# DM1098FFC_USB.net
KiCad netlist of a schematic drawn in Altium Designer
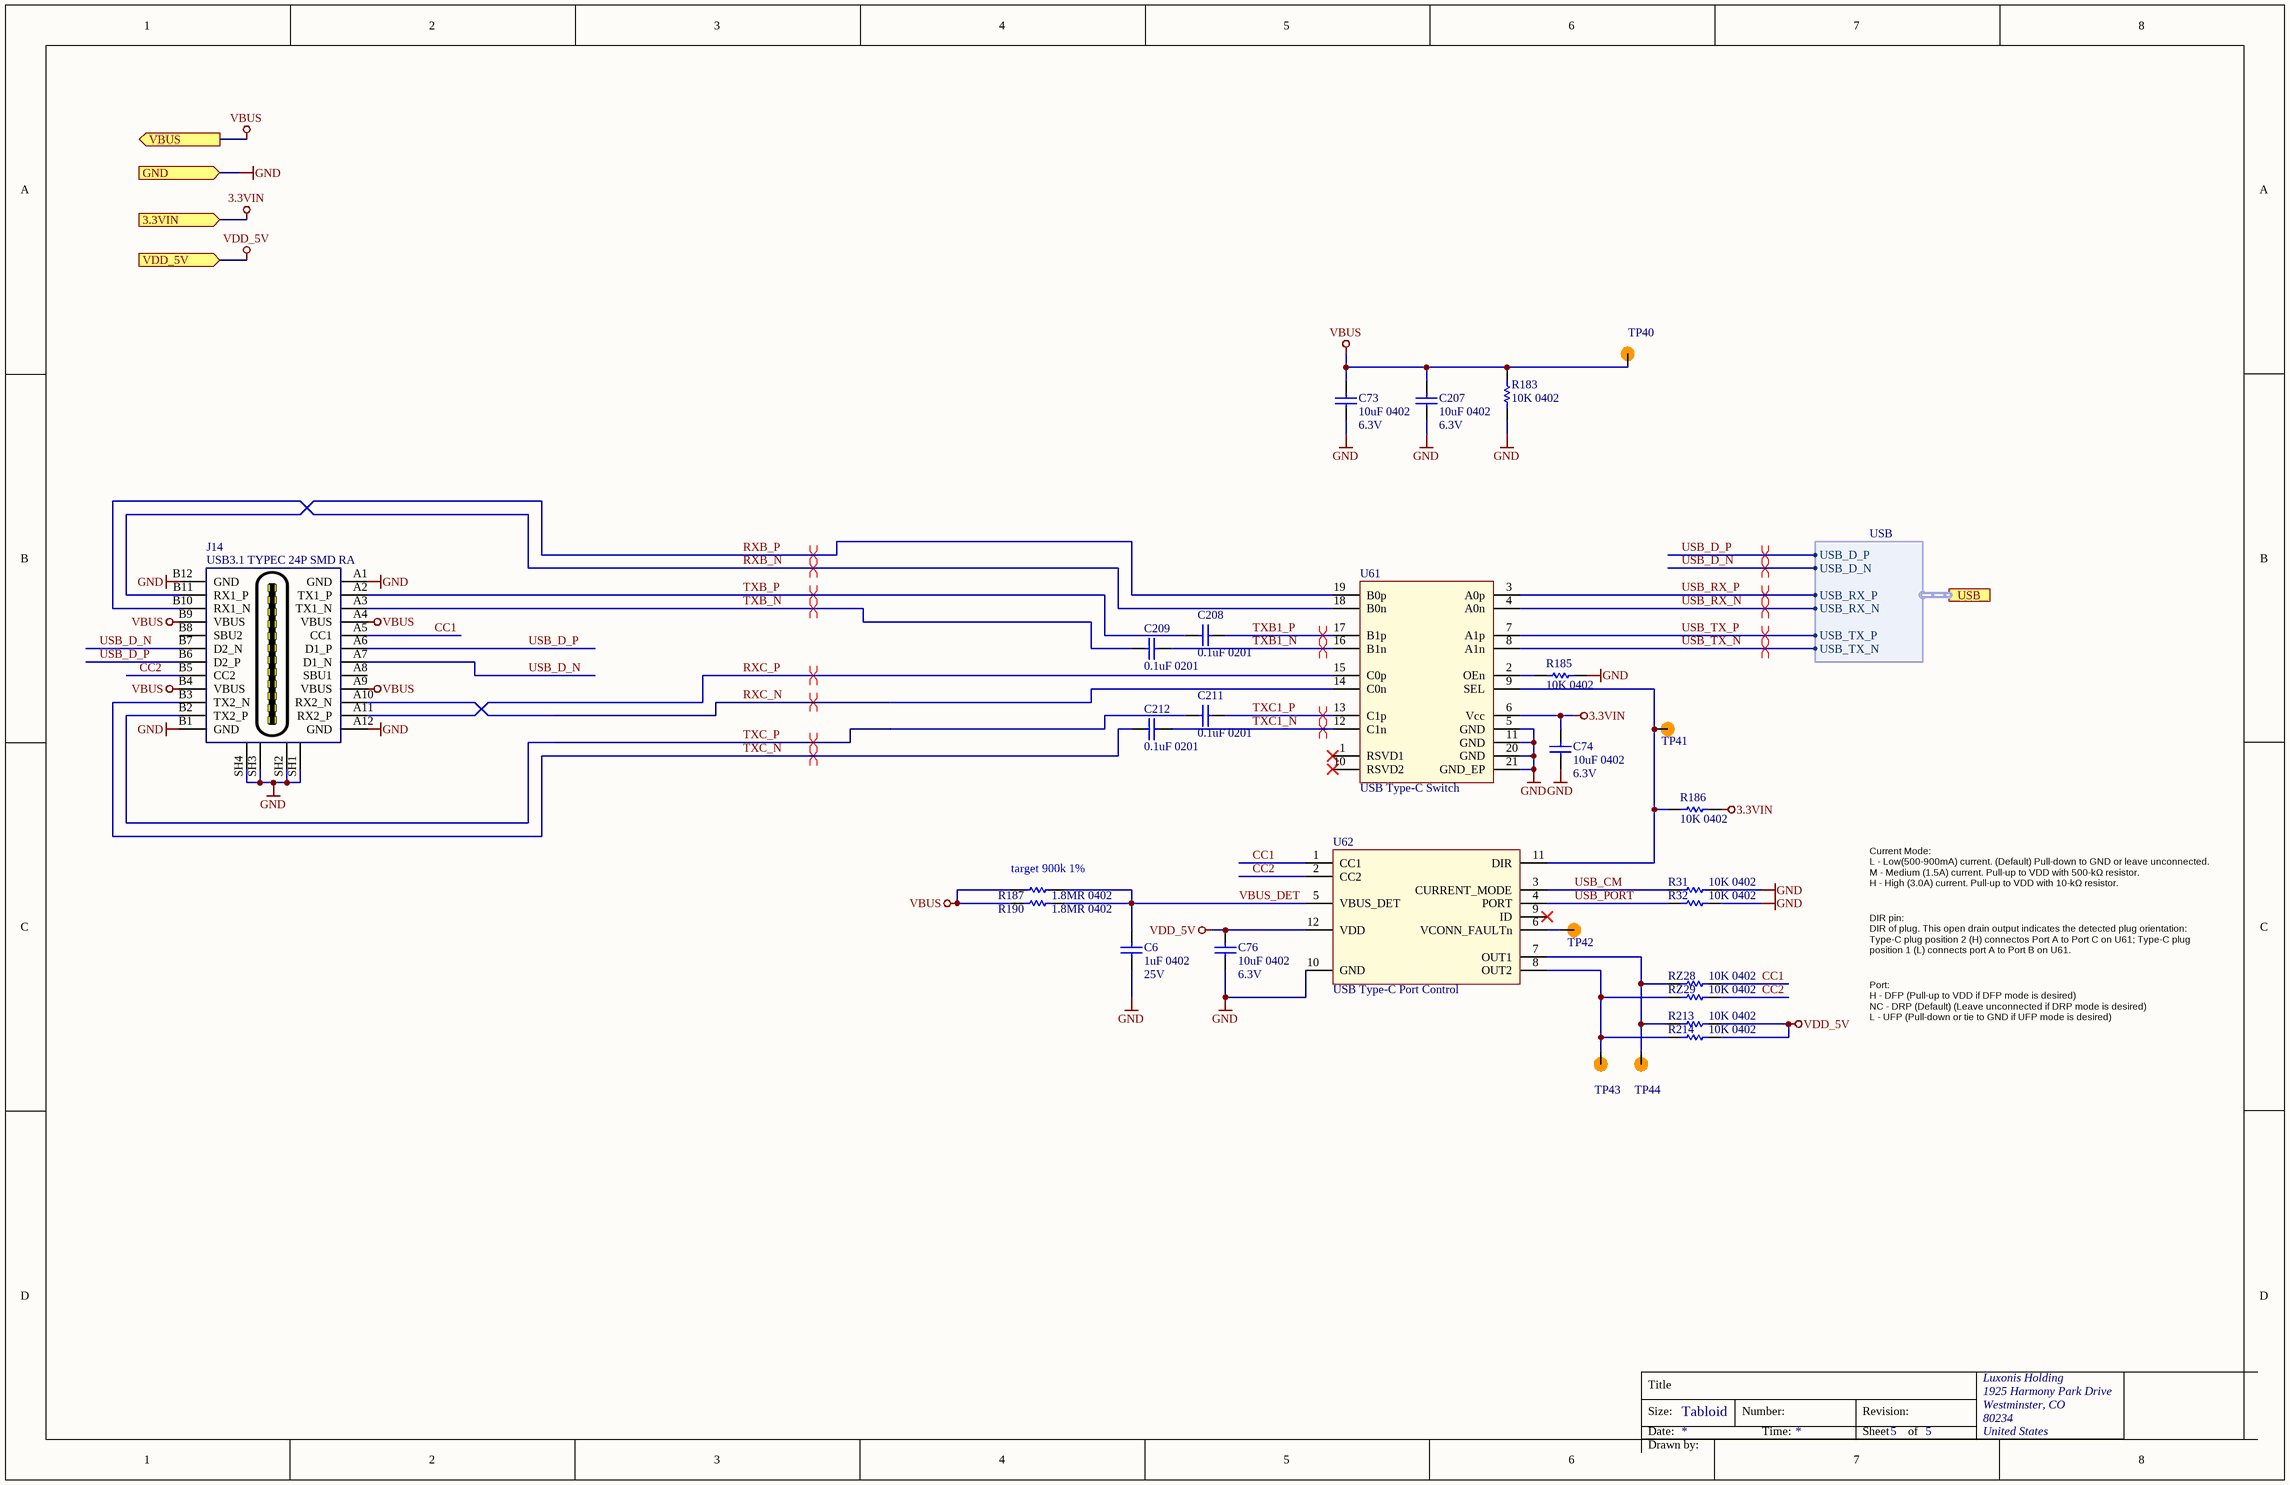
[diagram p0: DM1098FFC_USB.SchDoc]

(export (version "E")
  (design (tool "Eeschema 10.0.6"))
  (components
    (comp (ref "C6")
      (value "1uF 0402")
      (footprint "CAP_Altium_Vault_Generic:CAPC0402(1005)70_N")
      (description "CAP CER 1UF 25V X5R 0402 10%")
      (fields
        (field (name "TOLERANCE") "10%")
        (field (name "VOLTAGE") "25V")
        (field (name "VOLTAGE RATING") "25V")
      )
      (libsource (lib "LuxonisMaster") (part "GRM155R61E105KA12D"))
    )
    (comp (ref "C73")
      (value "10uF 0402")
      (footprint "CAP_Altium_Vault_Generic:CAPC0402(1005)70_N")
      (description "CAP CER 10UF 6.3V X5R 0402 20%")
      (fields (field (name "TOLERANCE") "20%") (field (name "VOLTAGE RATING") "6.3V"))
      (libsource (lib "LuxonisMaster") (part "GRM155R60J106ME15D"))
    )
    (comp (ref "C74")
      (value "10uF 0402")
      (footprint "CAP_Altium_Vault_Generic:CAPC0402(1005)70_N")
      (description "CAP CER 10UF 6.3V X5R 0402 20%")
      (fields (field (name "TOLERANCE") "20%") (field (name "VOLTAGE RATING") "6.3V"))
      (libsource (lib "LuxonisMaster") (part "GRM155R60J106ME15D"))
    )
    (comp (ref "C76")
      (value "10uF 0402")
      (footprint "CAP_Altium_Vault_Generic:CAPC0402(1005)70_N")
      (description "CAP CER 10UF 6.3V X5R 0402 20%")
      (fields (field (name "TOLERANCE") "20%") (field (name "VOLTAGE RATING") "6.3V"))
      (libsource (lib "LuxonisMaster") (part "GRM155R60J106ME15D"))
    )
    (comp (ref "C207")
      (value "10uF 0402")
      (footprint "CAP_Altium_Vault_Generic:CAPC0402(1005)70_N")
      (description "CAP CER 10UF 6.3V X5R 0402 20%")
      (fields (field (name "TOLERANCE") "20%") (field (name "VOLTAGE RATING") "6.3V"))
      (libsource (lib "LuxonisMaster") (part "GRM155R60J106ME15D"))
    )
    (comp (ref "C208")
      (value "0.1uF 0201")
      (footprint "CAP_Altium_Vault_Generic:CAPC0201(0603)33_L")
      (description "CAP CER 0.1UF 10V X5R 0201")
      (fields (field (name "TOLERANCE") "10%") (field (name "VOLTAGE") "10V"))
      (libsource (lib "LuxonisMaster") (part "GRM033R61A104KE15D"))
    )
    (comp (ref "C209")
      (value "0.1uF 0201")
      (footprint "CAP_Altium_Vault_Generic:CAPC0201(0603)33_L")
      (description "CAP CER 0.1UF 10V X5R 0201")
      (fields (field (name "TOLERANCE") "10%") (field (name "VOLTAGE") "10V"))
      (libsource (lib "LuxonisMaster") (part "GRM033R61A104KE15D"))
    )
    (comp (ref "C211")
      (value "0.1uF 0201")
      (footprint "CAP_Altium_Vault_Generic:CAPC0201(0603)33_L")
      (description "CAP CER 0.1UF 10V X5R 0201")
      (fields (field (name "TOLERANCE") "10%") (field (name "VOLTAGE") "10V"))
      (libsource (lib "LuxonisMaster") (part "GRM033R61A104KE15D"))
    )
    (comp (ref "C212")
      (value "0.1uF 0201")
      (footprint "CAP_Altium_Vault_Generic:CAPC0201(0603)33_L")
      (description "CAP CER 0.1UF 10V X5R 0201")
      (fields (field (name "TOLERANCE") "10%") (field (name "VOLTAGE") "10V"))
      (libsource (lib "LuxonisMaster") (part "GRM033R61A104KE15D"))
    )
    (comp (ref "J14")
      (value "USB3.1 TYPEC 24P SMD RA")
      (footprint "LuxonisMaster:105450-0101")
      (description "CONN RCP USB3.1 TYPEC 24P SMD RA")
      (libsource (lib "LuxonisMaster") (part "105450-0101"))
    )
    (comp (ref "R31")
      (value "10K 0402")
      (footprint "RES_Altium_Vault_Generic:RESC0402(1005)_N")
      (fields (field (name "TOLERANCE") "1%"))
      (libsource (lib "LuxonisMaster") (part "RC0402FR-1310KL"))
    )
    (comp (ref "R32")
      (value "10K 0402")
      (footprint "RES_Altium_Vault_Generic:RESC0402(1005)_N")
      (fields (field (name "TOLERANCE") "1%"))
      (libsource (lib "LuxonisMaster") (part "RC0402FR-1310KL"))
    )
    (comp (ref "R183")
      (value "10K 0402")
      (footprint "RES_Altium_Vault_Generic:RESC0402(1005)_N")
      (fields (field (name "TOLERANCE") "1%"))
      (libsource (lib "LuxonisMaster") (part "RC0402FR-1310KL"))
    )
    (comp (ref "R185")
      (value "10K 0402")
      (footprint "RES_Altium_Vault_Generic:RESC0402(1005)_N")
      (fields (field (name "TOLERANCE") "1%"))
      (libsource (lib "LuxonisMaster") (part "RC0402FR-1310KL"))
    )
    (comp (ref "R186")
      (value "10K 0402")
      (footprint "RES_Altium_Vault_Generic:RESC0402(1005)_N")
      (fields (field (name "TOLERANCE") "1%"))
      (libsource (lib "LuxonisMaster") (part "RC0402FR-1310KL"))
    )
    (comp (ref "R187")
      (value "1.8MR 0402")
      (footprint "RES_Altium_Vault_Generic:RESC0402(1005)_N")
      (description "RES SMD 1.8M OHM 1% 1/16W 0402")
      (fields (field (name "TOLERANCE") "1%"))
      (libsource (lib "LuxonisMaster") (part "CRCW04021M80FKED"))
    )
    (comp (ref "R190")
      (value "1.8MR 0402")
      (footprint "RES_Altium_Vault_Generic:RESC0402(1005)_N")
      (description "RES SMD 1.8M OHM 1% 1/16W 0402")
      (fields (field (name "TOLERANCE") "1%"))
      (libsource (lib "LuxonisMaster") (part "CRCW04021M80FKED"))
    )
    (comp (ref "R213")
      (value "10K 0402")
      (footprint "RES_Altium_Vault_Generic:RESC0402(1005)_N")
      (fields (field (name "TOLERANCE") "1%"))
      (libsource (lib "LuxonisMaster") (part "RC0402FR-1310KL"))
    )
    (comp (ref "R214")
      (value "10K 0402")
      (footprint "RES_Altium_Vault_Generic:RESC0402(1005)_N")
      (fields (field (name "TOLERANCE") "1%"))
      (libsource (lib "LuxonisMaster") (part "RC0402FR-1310KL"))
    )
    (comp (ref "RZ28")
      (value "10K 0402")
      (footprint "RES_Altium_Vault_Generic:RESC0402(1005)_N")
      (fields (field (name "TOLERANCE") "1%"))
      (libsource (lib "LuxonisMaster") (part "RC0402FR-1310KL"))
    )
    (comp (ref "RZ29")
      (value "10K 0402")
      (footprint "RES_Altium_Vault_Generic:RESC0402(1005)_N")
      (fields (field (name "TOLERANCE") "1%"))
      (libsource (lib "LuxonisMaster") (part "RC0402FR-1310KL"))
    )
    (comp (ref "TP40")
      (value "TP100_200_NS")
      (footprint "LuxonisMaster:TP100_200_NS")
      (libsource (lib "LuxonisMaster") (part "TEST_POINT"))
    )
    (comp (ref "TP41")
      (value "TP100_200_NS")
      (footprint "LuxonisMaster:TP100_200_NS")
      (libsource (lib "LuxonisMaster") (part "TEST_POINT"))
    )
    (comp (ref "TP42")
      (value "TP100_200_NS")
      (footprint "LuxonisMaster:TP100_200_NS")
      (libsource (lib "LuxonisMaster") (part "TEST_POINT"))
    )
    (comp (ref "TP43")
      (value "TP100_200_NS")
      (footprint "LuxonisMaster:TP100_200_NS")
      (libsource (lib "LuxonisMaster") (part "TEST_POINT"))
    )
    (comp (ref "TP44")
      (value "TP100_200_NS")
      (footprint "LuxonisMaster:TP100_200_NS")
      (libsource (lib "LuxonisMaster") (part "TEST_POINT"))
    )
    (comp (ref "U61")
      (value "USB Type-C Switch")
      (footprint "LuxonisMaster:HD3SS3212RKSR")
      (description "IC MUX 2:1 8 OHM 20VQFN")
      (libsource (lib "LuxonisMaster") (part "HD3SS3212RKSR"))
    )
    (comp (ref "U62")
      (value "USB Type-C Port Control")
      (footprint "LuxonisMaster:TUSB321RWBR")
      (description "IC USB PORT CONTROL TYPE-C 12X2Q")
      (libsource (lib "LuxonisMaster") (part "TUSB321RWBR"))
    )
  )
  (nets
    (net (code "2") (name "/CC1") (class "Default")
      (node (ref "J14") (pin "A5") (pinfunction "CC1_A5") (pintype "passive"))
      (node (ref "RZ28") (pin "2") (pinfunction "2_2") (pintype "passive"))
      (node (ref "U62") (pin "1") (pinfunction "CC1_1") (pintype "passive"))
    )
    (net (code "3") (name "/CC2") (class "Default")
      (node (ref "J14") (pin "B5") (pinfunction "CC2_B5") (pintype "passive"))
      (node (ref "RZ29") (pin "2") (pinfunction "2_2") (pintype "passive"))
      (node (ref "U62") (pin "2") (pinfunction "CC2_2") (pintype "passive"))
    )
    (net (code "4") (name "/RXB_N") (class "Default")
      (node (ref "J14") (pin "B10") (pinfunction "RX1_N_B10") (pintype "passive"))
      (node (ref "U61") (pin "18") (pinfunction "B0n_18") (pintype "passive"))
    )
    (net (code "5") (name "/RXB_P") (class "Default")
      (node (ref "J14") (pin "B11") (pinfunction "RX1_P_B11") (pintype "passive"))
      (node (ref "U61") (pin "19") (pinfunction "B0p_19") (pintype "passive"))
    )
    (net (code "6") (name "/RXC_N") (class "Default")
      (node (ref "J14") (pin "A10") (pinfunction "RX2_N_A10") (pintype "passive"))
      (node (ref "U61") (pin "14") (pinfunction "C0n_14") (pintype "passive"))
    )
    (net (code "7") (name "/RXC_P") (class "Default")
      (node (ref "J14") (pin "A11") (pinfunction "RX2_P_A11") (pintype "passive"))
      (node (ref "U61") (pin "15") (pinfunction "C0p_15") (pintype "passive"))
    )
    (net (code "8") (name "/TXB1_N") (class "Default")
      (node (ref "C209") (pin "2") (pinfunction "2_2") (pintype "passive"))
      (node (ref "U61") (pin "16") (pinfunction "B1n_16") (pintype "passive"))
    )
    (net (code "9") (name "/TXB1_P") (class "Default")
      (node (ref "C208") (pin "2") (pinfunction "2_2") (pintype "passive"))
      (node (ref "U61") (pin "17") (pinfunction "B1p_17") (pintype "passive"))
    )
    (net (code "10") (name "/TXB_N") (class "Default")
      (node (ref "C209") (pin "1") (pinfunction "1_1") (pintype "passive"))
      (node (ref "J14") (pin "A3") (pinfunction "TX1_N_A3") (pintype "passive"))
    )
    (net (code "11") (name "/TXB_P") (class "Default")
      (node (ref "C208") (pin "1") (pinfunction "1_1") (pintype "passive"))
      (node (ref "J14") (pin "A2") (pinfunction "TX1_P_A2") (pintype "passive"))
    )
    (net (code "12") (name "/TXC1_N") (class "Default")
      (node (ref "C212") (pin "2") (pinfunction "2_2") (pintype "passive"))
      (node (ref "U61") (pin "12") (pinfunction "C1n_12") (pintype "passive"))
    )
    (net (code "13") (name "/TXC1_P") (class "Default")
      (node (ref "C211") (pin "2") (pinfunction "2_2") (pintype "passive"))
      (node (ref "U61") (pin "13") (pinfunction "C1p_13") (pintype "passive"))
    )
    (net (code "14") (name "/TXC_N") (class "Default")
      (node (ref "C212") (pin "1") (pinfunction "1_1") (pintype "passive"))
      (node (ref "J14") (pin "B3") (pinfunction "TX2_N_B3") (pintype "passive"))
    )
    (net (code "15") (name "/TXC_P") (class "Default")
      (node (ref "C211") (pin "1") (pinfunction "1_1") (pintype "passive"))
      (node (ref "J14") (pin "B2") (pinfunction "TX2_P_B2") (pintype "passive"))
    )
    (net (code "16") (name "/USB_CM") (class "Default")
      (node (ref "R31") (pin "1") (pinfunction "1_1") (pintype "passive"))
      (node (ref "U62") (pin "3") (pinfunction "CURRENT_MODE_3") (pintype "passive"))
    )
    (net (code "17") (name "/USB_D_N") (class "Default")
      (node (ref "J14") (pin "A7") (pinfunction "D1_N_A7") (pintype "passive"))
      (node (ref "J14") (pin "B7") (pinfunction "D2_N_B7") (pintype "passive"))
    )
    (net (code "18") (name "/USB_D_P") (class "Default")
      (node (ref "J14") (pin "A6") (pinfunction "D1_P_A6") (pintype "passive"))
      (node (ref "J14") (pin "B6") (pinfunction "D2_P_B6") (pintype "passive"))
    )
    (net (code "19") (name "/USB_PORT") (class "Default")
      (node (ref "R32") (pin "1") (pinfunction "1_1") (pintype "passive"))
      (node (ref "U62") (pin "4") (pinfunction "PORT_4") (pintype "passive"))
    )
    (net (code "20") (name "/USB_RX_N") (class "Default")
      (node (ref "U61") (pin "4") (pinfunction "A0n_4") (pintype "passive"))
    )
    (net (code "21") (name "/USB_RX_P") (class "Default")
      (node (ref "U61") (pin "3") (pinfunction "A0p_3") (pintype "passive"))
    )
    (net (code "22") (name "/USB_TX_N") (class "Default")
      (node (ref "U61") (pin "8") (pinfunction "A1n_8") (pintype "passive"))
    )
    (net (code "23") (name "/USB_TX_P") (class "Default")
      (node (ref "U61") (pin "7") (pinfunction "A1p_7") (pintype "passive"))
    )
    (net (code "24") (name "/VBUS_DET") (class "Default")
      (node (ref "C6") (pin "2") (pinfunction "2_2") (pintype "passive"))
      (node (ref "R187") (pin "2") (pinfunction "2_2") (pintype "passive"))
      (node (ref "R190") (pin "2") (pinfunction "2_2") (pintype "passive"))
      (node (ref "U62") (pin "5") (pinfunction "VBUS_DET_5") (pintype "passive"))
    )
    (net (code "26") (name "3.3VIN") (class "Default")
      (node (ref "C74") (pin "2") (pinfunction "2_2") (pintype "passive"))
      (node (ref "R186") (pin "2") (pinfunction "2_2") (pintype "passive"))
      (node (ref "U61") (pin "6") (pinfunction "Vcc_6") (pintype "passive"))
    )
    (net (code "27") (name "GND") (class "Default")
      (node (ref "C207") (pin "1") (pinfunction "1_1") (pintype "passive"))
      (node (ref "C6") (pin "1") (pinfunction "1_1") (pintype "passive"))
      (node (ref "C73") (pin "1") (pinfunction "1_1") (pintype "passive"))
      (node (ref "C74") (pin "1") (pinfunction "1_1") (pintype "passive"))
      (node (ref "C76") (pin "1") (pinfunction "1_1") (pintype "passive"))
      (node (ref "J14") (pin "A1") (pinfunction "GND_A1") (pintype "passive"))
      (node (ref "J14") (pin "A12") (pinfunction "GND_A12") (pintype "passive"))
      (node (ref "J14") (pin "B1") (pinfunction "GND_B1") (pintype "passive"))
      (node (ref "J14") (pin "B12") (pinfunction "GND_B12") (pintype "passive"))
      (node (ref "J14") (pin "SH1") (pinfunction "SH_SH1") (pintype "passive"))
      (node (ref "J14") (pin "SH2") (pinfunction "SH_SH2") (pintype "passive"))
      (node (ref "J14") (pin "SH3") (pinfunction "SH_SH3") (pintype "passive"))
      (node (ref "J14") (pin "SH4") (pinfunction "SH_SH4") (pintype "passive"))
      (node (ref "R183") (pin "1") (pinfunction "1_1") (pintype "passive"))
      (node (ref "R185") (pin "2") (pinfunction "2_2") (pintype "passive"))
      (node (ref "R31") (pin "2") (pinfunction "2_2") (pintype "passive"))
      (node (ref "R32") (pin "2") (pinfunction "2_2") (pintype "passive"))
      (node (ref "U61") (pin "11") (pinfunction "GND_11") (pintype "passive"))
      (node (ref "U61") (pin "20") (pinfunction "GND_20") (pintype "passive"))
      (node (ref "U61") (pin "21") (pinfunction "GND_EP_21") (pintype "passive"))
      (node (ref "U61") (pin "5") (pinfunction "GND_5") (pintype "passive"))
      (node (ref "U62") (pin "10") (pinfunction "GND_10") (pintype "passive"))
    )
    (net (code "28") (name "Net-(U61-OEn)") (class "Default")
      (node (ref "R185") (pin "1") (pinfunction "1_1") (pintype "passive"))
      (node (ref "U61") (pin "2") (pinfunction "OEn_2") (pintype "passive"))
    )
    (net (code "29") (name "Net-(U61-SEL)") (class "Default")
      (node (ref "R186") (pin "1") (pinfunction "1_1") (pintype "passive"))
      (node (ref "TP41") (pin "1") (pintype "passive"))
      (node (ref "U61") (pin "9") (pinfunction "SEL_9") (pintype "passive"))
      (node (ref "U62") (pin "11") (pinfunction "DIR_11") (pintype "passive"))
    )
    (net (code "30") (name "Net-(U62-OUT1)") (class "Default")
      (node (ref "R213") (pin "1") (pinfunction "1_1") (pintype "passive"))
      (node (ref "RZ28") (pin "1") (pinfunction "1_1") (pintype "passive"))
      (node (ref "TP44") (pin "1") (pintype "passive"))
      (node (ref "U62") (pin "7") (pinfunction "OUT1_7") (pintype "passive"))
    )
    (net (code "31") (name "Net-(U62-OUT2)") (class "Default")
      (node (ref "R214") (pin "1") (pinfunction "1_1") (pintype "passive"))
      (node (ref "RZ29") (pin "1") (pinfunction "1_1") (pintype "passive"))
      (node (ref "TP43") (pin "1") (pintype "passive"))
      (node (ref "U62") (pin "8") (pinfunction "OUT2_8") (pintype "passive"))
    )
    (net (code "32") (name "Net-(U62-VCONN_FAULTn)") (class "Default")
      (node (ref "TP42") (pin "1") (pintype "passive"))
      (node (ref "U62") (pin "6") (pinfunction "VCONN_FAULTn_6") (pintype "passive"))
    )
    (net (code "33") (name "VBUS") (class "Default")
      (node (ref "C207") (pin "2") (pinfunction "2_2") (pintype "passive"))
      (node (ref "C73") (pin "2") (pinfunction "2_2") (pintype "passive"))
      (node (ref "J14") (pin "A4") (pinfunction "VBUS_A4") (pintype "passive"))
      (node (ref "J14") (pin "A9") (pinfunction "VBUS_A9") (pintype "passive"))
      (node (ref "J14") (pin "B4") (pinfunction "VBUS_B4") (pintype "passive"))
      (node (ref "J14") (pin "B9") (pinfunction "VBUS_B9") (pintype "passive"))
      (node (ref "R183") (pin "2") (pinfunction "2_2") (pintype "passive"))
      (node (ref "R187") (pin "1") (pinfunction "1_1") (pintype "passive"))
      (node (ref "R190") (pin "1") (pinfunction "1_1") (pintype "passive"))
      (node (ref "TP40") (pin "1") (pintype "passive"))
    )
    (net (code "34") (name "VDD_5V") (class "Default")
      (node (ref "C76") (pin "2") (pinfunction "2_2") (pintype "passive"))
      (node (ref "R213") (pin "2") (pinfunction "2_2") (pintype "passive"))
      (node (ref "R214") (pin "2") (pinfunction "2_2") (pintype "passive"))
      (node (ref "U62") (pin "12") (pinfunction "VDD_12") (pintype "passive"))
    )
    (net (code "35") (name "unconnected-(J14-SBU1-PadA8)") (class "Default")
      (node (ref "J14") (pin "A8") (pinfunction "SBU1_A8") (pintype "passive"))
    )
    (net (code "36") (name "unconnected-(J14-SBU2-PadB8)") (class "Default")
      (node (ref "J14") (pin "B8") (pinfunction "SBU2_B8") (pintype "passive"))
    )
    (net (code "37") (name "unconnected-(U61-RSVD1-Pad1)") (class "Default")
      (node (ref "U61") (pin "1") (pinfunction "RSVD1_1") (pintype "passive+no_connect"))
    )
    (net (code "38") (name "unconnected-(U61-RSVD2-Pad10)") (class "Default")
      (node (ref "U61") (pin "10") (pinfunction "RSVD2_10") (pintype "passive+no_connect"))
    )
    (net (code "39") (name "unconnected-(U62-ID-Pad9)") (class "Default")
      (node (ref "U62") (pin "9") (pinfunction "ID_9") (pintype "passive+no_connect"))
    )
  )
)
